# uOhm_Schematic.net
KiCad netlist of a schematic drawn in EasyEDA
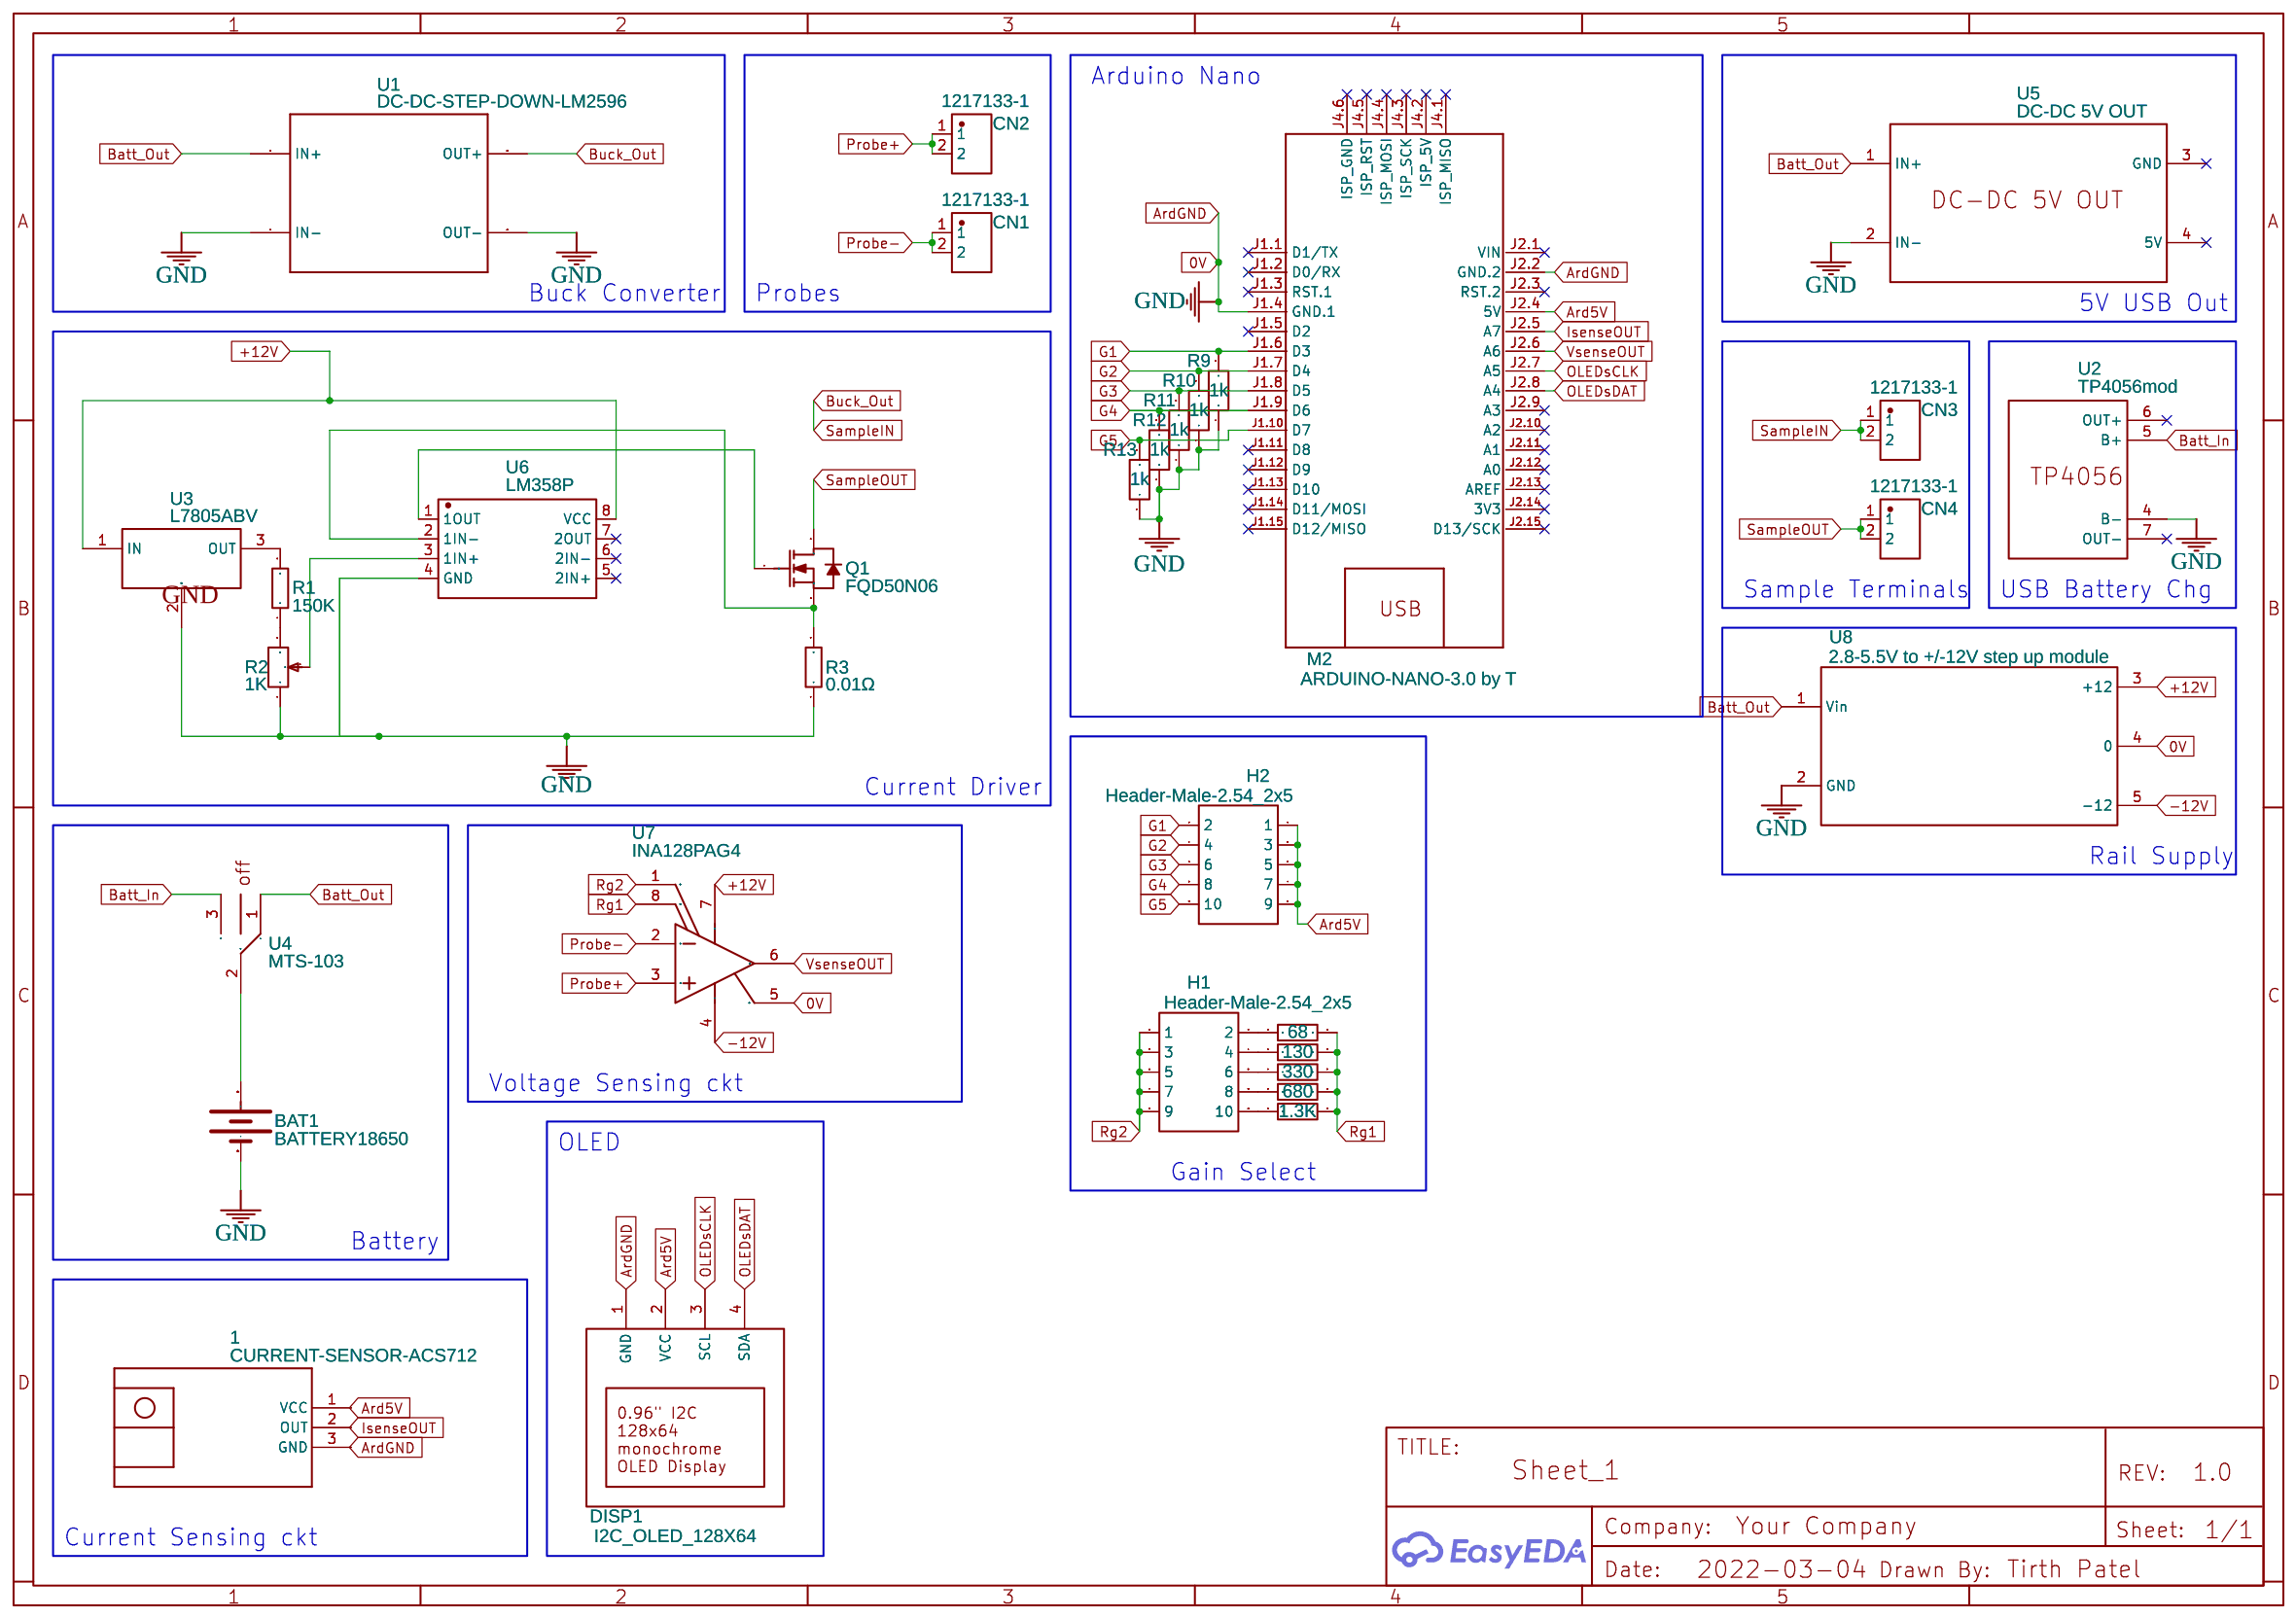
[diagram p0: schematic sheet]

(export (version "E")
  (design (tool "Eeschema 10.0.6"))
  (components
    (comp (ref "1") (value "CURRENT-SENSOR-ACS712") (libsource (lib "") (part "CURRENT-SENSOR-ACS712")))
    (comp (ref "BAT1") (value "BATTERY18650") (libsource (lib "") (part "BATTERY18650")))
    (comp (ref "CN1")
      (value "1217133-1")
      (fields (field (name "BOM_Supplier Part") "C133061"))
      (libsource (lib "") (part "1217133-1"))
    )
    (comp (ref "CN2")
      (value "1217133-1")
      (fields (field (name "BOM_Supplier Part") "C133061"))
      (libsource (lib "") (part "1217133-1"))
    )
    (comp (ref "CN3")
      (value "1217133-1")
      (fields (field (name "BOM_Supplier Part") "C133061"))
      (libsource (lib "") (part "1217133-1"))
    )
    (comp (ref "CN4")
      (value "1217133-1")
      (fields (field (name "BOM_Supplier Part") "C133061"))
      (libsource (lib "") (part "1217133-1"))
    )
    (comp (ref "DISP1") (value "I2C_OLED_128X64") (libsource (lib "") (part "I2C_OLED_128X64")))
    (comp (ref "H1")
      (value "Header-Male-2.54_2x5")
      (fields
        (field (name "BOM_Manufacturer Part") "2*5pHeaders  Pins 2.54mm")
        (field (name "BOM_Supplier Part") "C28207")
      )
      (libsource (lib "") (part "Header-Male-2.54_2x5"))
    )
    (comp (ref "H2")
      (value "Header-Male-2.54_2x5")
      (fields
        (field (name "BOM_Manufacturer Part") "2*5pHeaders  Pins 2.54mm")
        (field (name "BOM_Supplier Part") "C28207")
      )
      (libsource (lib "") (part "Header-Male-2.54_2x5_1"))
    )
    (comp (ref "M2") (value "ARDUINO-NANO-3.0 by T") (libsource (lib "") (part "ARDUINO-NANO-3.0 by T")))
    (comp (ref "Q1")
      (value "FQD50N06")
      (fields (field (name "BOM_Supplier Part") "C725048"))
      (libsource (lib "") (part "FQD50N06"))
    )
    (comp (ref "R1")
      (value "150K")
      (fields
        (field (name "BOM_Manufacturer Part") "MFR0W4F1503A50")
        (field (name "BOM_Supplier Part") "C58618")
      )
      (libsource (lib "") (part "MFR0W4F1503A50"))
    )
    (comp (ref "R2")
      (value "1K")
      (fields
        (field (name "BOM_Manufacturer Part") "3296W-1-102LF")
        (field (name "BOM_Supplier Part") "C57089")
      )
      (libsource (lib "") (part "3296W-1-102LF"))
    )
    (comp (ref "R3")
      (value "0.01Ω")
      (fields
        (field (name "BOM_Manufacturer Part") "LR2512-23R010F4")
        (field (name "BOM_Supplier Part") "C323803")
      )
      (libsource (lib "") (part "LR2512-23R010F4"))
    )
    (comp (ref "R4")
      (value "330")
      (fields
        (field (name "BOM_Manufacturer Part") "MFR1WSFTE52-330R")
        (field (name "BOM_Supplier Part") "C172941")
      )
      (libsource (lib "") (part "MFR1WSFTE52-330R"))
    )
    (comp (ref "R5")
      (value "130")
      (fields
        (field (name "BOM_Manufacturer Part") "RD50T5131J")
        (field (name "BOM_Supplier Part") "C167536")
      )
      (libsource (lib "") (part "RD50T5131J"))
    )
    (comp (ref "R6")
      (value "680")
      (fields
        (field (name "BOM_Manufacturer Part") "MFR0W4F6800A50")
        (field (name "BOM_Supplier Part") "C58599")
      )
      (libsource (lib "") (part "MFR0W4F6800A50"))
    )
    (comp (ref "R7")
      (value "68")
      (fields
        (field (name "BOM_Manufacturer Part") "RSS02J68R0A520NH")
        (field (name "BOM_Supplier Part") "C274837")
      )
      (libsource (lib "") (part "RSS02J68R0A520NH"))
    )
    (comp (ref "R8")
      (value "1.3K")
      (fields
        (field (name "BOM_Manufacturer Part") "CFR0W4J0132A50")
        (field (name "BOM_Supplier Part") "C70828")
      )
      (libsource (lib "") (part "CFR0W4J0132A50"))
    )
    (comp (ref "R9")
      (value "1k")
      (fields
        (field (name "BOM_Manufacturer Part") "CFR0W4J0102A50")
        (field (name "BOM_Supplier Part") "C66649")
      )
      (libsource (lib "") (part "CFR0W4J0102A50_C66649"))
    )
    (comp (ref "R10")
      (value "1k")
      (fields
        (field (name "BOM_Manufacturer Part") "CFR0W4J0102A50")
        (field (name "BOM_Supplier Part") "C66649")
      )
      (libsource (lib "") (part "CFR0W4J0102A50_C66649"))
    )
    (comp (ref "R11")
      (value "1k")
      (fields
        (field (name "BOM_Manufacturer Part") "CFR0W4J0102A50")
        (field (name "BOM_Supplier Part") "C66649")
      )
      (libsource (lib "") (part "CFR0W4J0102A50_C66649"))
    )
    (comp (ref "R12")
      (value "1k")
      (fields
        (field (name "BOM_Manufacturer Part") "CFR0W4J0102A50")
        (field (name "BOM_Supplier Part") "C66649")
      )
      (libsource (lib "") (part "CFR0W4J0102A50_C66649"))
    )
    (comp (ref "R13")
      (value "1k")
      (fields
        (field (name "BOM_Manufacturer Part") "CFR0W4J0102A50")
        (field (name "BOM_Supplier Part") "C66649")
      )
      (libsource (lib "") (part "CFR0W4J0102A50_C66649"))
    )
    (comp (ref "U1") (value "DC-DC-STEP-DOWN-LM2596") (libsource (lib "") (part "DC-DC-STEP-DOWN-LM2596")))
    (comp (ref "U2")
      (value "TP4056mod")
      (fields (field (name "BOM_Manufacturer Part") "TP4056-protect"))
      (libsource (lib "") (part "TP4056mod"))
    )
    (comp (ref "U3")
      (value "L7805ABV")
      (fields (field (name "BOM_Supplier Part") "C16807"))
      (libsource (lib "") (part "L7805ABV"))
    )
    (comp (ref "U4") (value "MTS-103") (libsource (lib "") (part "MTS-103")))
    (comp (ref "U5")
      (value "DC-DC 5V OUT")
      (fields (field (name "BOM_Manufacturer Part") "STEP UP"))
      (libsource (lib "") (part "DC-DC 5V OUT"))
    )
    (comp (ref "U6")
      (value "LM358P")
      (fields (field (name "BOM_Supplier Part") "C5213"))
      (libsource (lib "") (part "LM358P"))
    )
    (comp (ref "U7")
      (value "INA128PAG4")
      (fields (field (name "BOM_Supplier Part") "C28937"))
      (libsource (lib "") (part "INA128PAG4"))
    )
    (comp (ref "U8")
      (value "2.8-5.5V to +/-12V step up module")
      (libsource (lib "") (part "2.8-5.5V to +/-12V step up module"))
    )
  )
  (nets
    (net (code "1") (name "+12V") (class "Default")
      (node (ref "U3") (pin "1") (pinfunction "IN_1") (pintype "passive"))
      (node (ref "U6") (pin "8") (pinfunction "VCC_8") (pintype "unspecified"))
      (node (ref "U7") (pin "7") (pinfunction "V+_7") (pintype "passive"))
      (node (ref "U8") (pin "3") (pinfunction "+12_3") (pintype "unspecified"))
    )
    (net (code "2") (name "-12V") (class "Default")
      (node (ref "U7") (pin "4") (pinfunction "V-_4") (pintype "passive"))
      (node (ref "U8") (pin "5") (pinfunction "-12_5") (pintype "unspecified"))
    )
    (net (code "3") (name "0V") (class "Default")
      (node (ref "1") (pin "3") (pinfunction "GND_3") (pintype "bidirectional"))
      (node (ref "BAT1") (pin "GND@1") (pinfunction "-_GND@1") (pintype "passive"))
      (node (ref "DISP1") (pin "1") (pinfunction "GND_1") (pintype "unspecified"))
      (node (ref "M2") (pin "J1.4") (pinfunction "GND.1_J1.4") (pintype "bidirectional"))
      (node (ref "M2") (pin "J2.2") (pinfunction "GND.2_J2.2") (pintype "bidirectional"))
      (node (ref "R10") (pin "1") (pinfunction "1_1") (pintype "unspecified"))
      (node (ref "R11") (pin "1") (pinfunction "1_1") (pintype "unspecified"))
      (node (ref "R12") (pin "1") (pinfunction "1_1") (pintype "unspecified"))
      (node (ref "R13") (pin "1") (pinfunction "1_1") (pintype "unspecified"))
      (node (ref "R2") (pin "1") (pinfunction "1_1") (pintype "input"))
      (node (ref "R3") (pin "1") (pinfunction "1_1") (pintype "unspecified"))
      (node (ref "R9") (pin "1") (pinfunction "1_1") (pintype "unspecified"))
      (node (ref "U1") (pin "IN-") (pinfunction "IN-_IN-") (pintype "unspecified"))
      (node (ref "U1") (pin "OUT-") (pinfunction "OUT-_OUT-") (pintype "unspecified"))
      (node (ref "U2") (pin "4") (pinfunction "B-_4") (pintype "unspecified"))
      (node (ref "U3") (pin "2") (pinfunction "GND_2") (pintype "passive"))
      (node (ref "U5") (pin "2") (pinfunction "IN-_2") (pintype "unspecified"))
      (node (ref "U6") (pin "4") (pinfunction "GND_4") (pintype "unspecified"))
      (node (ref "U7") (pin "5") (pinfunction "REF_5") (pintype "unspecified"))
      (node (ref "U8") (pin "2") (pinfunction "GND_2") (pintype "unspecified"))
      (node (ref "U8") (pin "4") (pinfunction "0_4") (pintype "unspecified"))
    )
    (net (code "4") (name "Ard5V") (class "Default")
      (node (ref "1") (pin "1") (pinfunction "VCC_1") (pintype "bidirectional"))
      (node (ref "DISP1") (pin "2") (pinfunction "VCC_2") (pintype "unspecified"))
      (node (ref "H2") (pin "1") (pinfunction "1_1") (pintype "input"))
      (node (ref "H2") (pin "3") (pinfunction "3_3") (pintype "input"))
      (node (ref "H2") (pin "5") (pinfunction "5_5") (pintype "input"))
      (node (ref "H2") (pin "7") (pinfunction "7_7") (pintype "input"))
      (node (ref "H2") (pin "9") (pinfunction "9_9") (pintype "input"))
      (node (ref "M2") (pin "J2.4") (pinfunction "5V_J2.4") (pintype "bidirectional"))
    )
    (net (code "5") (name "Batt_In") (class "Default")
      (node (ref "U2") (pin "5") (pinfunction "B+_5") (pintype "unspecified"))
      (node (ref "U4") (pin "3") (pinfunction "3_3") (pintype "unspecified"))
    )
    (net (code "6") (name "Batt_Out") (class "Default")
      (node (ref "U1") (pin "IN+") (pinfunction "IN+_IN+") (pintype "unspecified"))
      (node (ref "U4") (pin "1") (pinfunction "1_1") (pintype "unspecified"))
      (node (ref "U5") (pin "1") (pinfunction "IN+_1") (pintype "unspecified"))
      (node (ref "U8") (pin "1") (pinfunction "Vin_1") (pintype "unspecified"))
    )
    (net (code "7") (name "Buck_Out") (class "Default")
      (node (ref "CN3") (pin "1") (pinfunction "1_1") (pintype "unspecified"))
      (node (ref "CN3") (pin "2") (pinfunction "2_2") (pintype "unspecified"))
      (node (ref "U1") (pin "OUT+") (pinfunction "OUT+_OUT+") (pintype "unspecified"))
    )
    (net (code "8") (name "G1") (class "Default")
      (node (ref "H2") (pin "2") (pinfunction "2_2") (pintype "input"))
      (node (ref "M2") (pin "J1.6") (pinfunction "D3_J1.6") (pintype "bidirectional"))
      (node (ref "R9") (pin "2") (pinfunction "2_2") (pintype "unspecified"))
    )
    (net (code "9") (name "G2") (class "Default")
      (node (ref "H2") (pin "4") (pinfunction "4_4") (pintype "input"))
      (node (ref "M2") (pin "J1.7") (pinfunction "D4_J1.7") (pintype "bidirectional"))
      (node (ref "R10") (pin "2") (pinfunction "2_2") (pintype "unspecified"))
    )
    (net (code "10") (name "G3") (class "Default")
      (node (ref "H2") (pin "6") (pinfunction "6_6") (pintype "input"))
      (node (ref "M2") (pin "J1.8") (pinfunction "D5_J1.8") (pintype "bidirectional"))
      (node (ref "R11") (pin "2") (pinfunction "2_2") (pintype "unspecified"))
    )
    (net (code "11") (name "G4") (class "Default")
      (node (ref "H2") (pin "8") (pinfunction "8_8") (pintype "input"))
      (node (ref "M2") (pin "J1.9") (pinfunction "D6_J1.9") (pintype "bidirectional"))
      (node (ref "R12") (pin "2") (pinfunction "2_2") (pintype "unspecified"))
    )
    (net (code "12") (name "G5") (class "Default")
      (node (ref "H2") (pin "10") (pinfunction "10_10") (pintype "input"))
      (node (ref "M2") (pin "J1.10") (pinfunction "D7_J1.10") (pintype "bidirectional"))
      (node (ref "R13") (pin "2") (pinfunction "2_2") (pintype "unspecified"))
    )
    (net (code "13") (name "IsenseOUT") (class "Default")
      (node (ref "1") (pin "2") (pinfunction "OUT_2") (pintype "bidirectional"))
      (node (ref "M2") (pin "J2.5") (pinfunction "A7_J2.5") (pintype "bidirectional"))
    )
    (net (code "14") (name "Net-(BAT1-+)") (class "Default")
      (node (ref "BAT1") (pin "PWR@1") (pinfunction "+_PWR@1") (pintype "passive"))
      (node (ref "U4") (pin "2") (pinfunction "2_2") (pintype "unspecified"))
    )
    (net (code "15") (name "Net-(H1-Pad2)") (class "Default")
      (node (ref "H1") (pin "2") (pinfunction "2_2") (pintype "input"))
      (node (ref "R7") (pin "1") (pinfunction "1_1") (pintype "unspecified"))
    )
    (net (code "16") (name "Net-(H1-Pad4)") (class "Default")
      (node (ref "H1") (pin "4") (pinfunction "4_4") (pintype "input"))
      (node (ref "R5") (pin "1") (pinfunction "1_1") (pintype "unspecified"))
    )
    (net (code "17") (name "Net-(H1-Pad6)") (class "Default")
      (node (ref "H1") (pin "6") (pinfunction "6_6") (pintype "input"))
      (node (ref "R4") (pin "1") (pinfunction "1_1") (pintype "unspecified"))
    )
    (net (code "18") (name "Net-(H1-Pad8)") (class "Default")
      (node (ref "H1") (pin "8") (pinfunction "8_8") (pintype "input"))
      (node (ref "R6") (pin "1") (pinfunction "1_1") (pintype "input"))
    )
    (net (code "19") (name "Net-(H1-Pad10)") (class "Default")
      (node (ref "H1") (pin "10") (pinfunction "10_10") (pintype "input"))
      (node (ref "R8") (pin "1") (pinfunction "1_1") (pintype "input"))
    )
    (net (code "20") (name "Net-(Q1-G)") (class "Default")
      (node (ref "Q1") (pin "1") (pinfunction "G_1") (pintype "unspecified"))
      (node (ref "U6") (pin "1") (pinfunction "1OUT_1") (pintype "unspecified"))
    )
    (net (code "21") (name "Net-(Q1-S)") (class "Default")
      (node (ref "Q1") (pin "3") (pinfunction "S_3") (pintype "unspecified"))
      (node (ref "R3") (pin "2") (pinfunction "2_2") (pintype "unspecified"))
      (node (ref "U6") (pin "2") (pinfunction "1IN-_2") (pintype "unspecified"))
    )
    (net (code "22") (name "Net-(R1-Pad1)") (class "Default")
      (node (ref "R1") (pin "1") (pinfunction "1_1") (pintype "input"))
      (node (ref "R2") (pin "3") (pinfunction "3_3") (pintype "input"))
    )
    (net (code "23") (name "Net-(U3-OUT)") (class "Default")
      (node (ref "R1") (pin "2") (pinfunction "2_2") (pintype "input"))
      (node (ref "U3") (pin "3") (pinfunction "OUT_3") (pintype "passive"))
    )
    (net (code "24") (name "Net-(U6-1IN+)") (class "Default")
      (node (ref "R2") (pin "2") (pinfunction "2_2") (pintype "input"))
      (node (ref "U6") (pin "3") (pinfunction "1IN+_3") (pintype "unspecified"))
    )
    (net (code "25") (name "OLEDsCLK") (class "Default")
      (node (ref "DISP1") (pin "3") (pinfunction "SCL_3") (pintype "unspecified"))
      (node (ref "M2") (pin "J2.7") (pinfunction "A5_J2.7") (pintype "bidirectional"))
    )
    (net (code "26") (name "OLEDsDAT") (class "Default")
      (node (ref "DISP1") (pin "4") (pinfunction "SDA_4") (pintype "unspecified"))
      (node (ref "M2") (pin "J2.8") (pinfunction "A4_J2.8") (pintype "bidirectional"))
    )
    (net (code "27") (name "Probe+") (class "Default")
      (node (ref "CN2") (pin "1") (pinfunction "1_1") (pintype "unspecified"))
      (node (ref "CN2") (pin "2") (pinfunction "2_2") (pintype "unspecified"))
      (node (ref "U7") (pin "3") (pinfunction "VIN+_3") (pintype "unspecified"))
    )
    (net (code "28") (name "Probe-") (class "Default")
      (node (ref "CN1") (pin "1") (pinfunction "1_1") (pintype "unspecified"))
      (node (ref "CN1") (pin "2") (pinfunction "2_2") (pintype "unspecified"))
      (node (ref "U7") (pin "2") (pinfunction "VIN-_2") (pintype "unspecified"))
    )
    (net (code "29") (name "Rg1") (class "Default")
      (node (ref "R4") (pin "2") (pinfunction "2_2") (pintype "unspecified"))
      (node (ref "R5") (pin "2") (pinfunction "2_2") (pintype "unspecified"))
      (node (ref "R6") (pin "2") (pinfunction "2_2") (pintype "input"))
      (node (ref "R7") (pin "2") (pinfunction "2_2") (pintype "unspecified"))
      (node (ref "R8") (pin "2") (pinfunction "2_2") (pintype "input"))
      (node (ref "U7") (pin "8") (pinfunction "RG_8") (pintype "unspecified"))
    )
    (net (code "30") (name "Rg2") (class "Default")
      (node (ref "H1") (pin "1") (pinfunction "1_1") (pintype "input"))
      (node (ref "H1") (pin "3") (pinfunction "3_3") (pintype "input"))
      (node (ref "H1") (pin "5") (pinfunction "5_5") (pintype "input"))
      (node (ref "H1") (pin "7") (pinfunction "7_7") (pintype "input"))
      (node (ref "H1") (pin "9") (pinfunction "9_9") (pintype "input"))
      (node (ref "U7") (pin "1") (pinfunction "RG_1") (pintype "unspecified"))
    )
    (net (code "31") (name "SampleOUT") (class "Default")
      (node (ref "CN4") (pin "1") (pinfunction "1_1") (pintype "unspecified"))
      (node (ref "CN4") (pin "2") (pinfunction "2_2") (pintype "unspecified"))
      (node (ref "Q1") (pin "2") (pinfunction "D_2") (pintype "unspecified"))
    )
    (net (code "32") (name "VsenseOUT") (class "Default")
      (node (ref "M2") (pin "J2.6") (pinfunction "A6_J2.6") (pintype "bidirectional"))
      (node (ref "U7") (pin "6") (pinfunction "VO_6") (pintype "output"))
    )
    (net (code "33") (name "unconnected-(M2-3V3-PadJ2.14)") (class "Default")
      (node (ref "M2") (pin "J2.14") (pinfunction "3V3_J2.14") (pintype "bidirectional+no_connect"))
    )
    (net (code "34") (name "unconnected-(M2-A0-PadJ2.12)") (class "Default")
      (node (ref "M2") (pin "J2.12") (pinfunction "A0_J2.12") (pintype "bidirectional+no_connect"))
    )
    (net (code "35") (name "unconnected-(M2-A1-PadJ2.11)") (class "Default")
      (node (ref "M2") (pin "J2.11") (pinfunction "A1_J2.11") (pintype "bidirectional+no_connect"))
    )
    (net (code "36") (name "unconnected-(M2-A2-PadJ2.10)") (class "Default")
      (node (ref "M2") (pin "J2.10") (pinfunction "A2_J2.10") (pintype "bidirectional+no_connect"))
    )
    (net (code "37") (name "unconnected-(M2-A3-PadJ2.9)") (class "Default")
      (node (ref "M2") (pin "J2.9") (pinfunction "A3_J2.9") (pintype "bidirectional+no_connect"))
    )
    (net (code "38") (name "unconnected-(M2-AREF-PadJ2.13)") (class "Default")
      (node (ref "M2") (pin "J2.13") (pinfunction "AREF_J2.13") (pintype "bidirectional+no_connect"))
    )
    (net (code "39") (name "unconnected-(M2-D0{slash}RX-PadJ1.2)") (class "Default")
      (node (ref "M2") (pin "J1.2") (pinfunction "D0/RX_J1.2") (pintype "bidirectional+no_connect"))
    )
    (net (code "40") (name "unconnected-(M2-D1{slash}TX-PadJ1.1)") (class "Default")
      (node (ref "M2") (pin "J1.1") (pinfunction "D1/TX_J1.1") (pintype "bidirectional+no_connect"))
    )
    (net (code "41") (name "unconnected-(M2-D2-PadJ1.5)") (class "Default")
      (node (ref "M2") (pin "J1.5") (pinfunction "D2_J1.5") (pintype "bidirectional+no_connect"))
    )
    (net (code "42") (name "unconnected-(M2-D8-PadJ1.11)") (class "Default")
      (node (ref "M2") (pin "J1.11") (pinfunction "D8_J1.11") (pintype "bidirectional+no_connect"))
    )
    (net (code "43") (name "unconnected-(M2-D9-PadJ1.12)") (class "Default")
      (node (ref "M2") (pin "J1.12") (pinfunction "D9_J1.12") (pintype "bidirectional+no_connect"))
    )
    (net (code "44") (name "unconnected-(M2-D10-PadJ1.13)") (class "Default")
      (node (ref "M2") (pin "J1.13") (pinfunction "D10_J1.13") (pintype "bidirectional+no_connect"))
    )
    (net (code "45") (name "unconnected-(M2-D11{slash}MOSI-PadJ1.14)") (class "Default")
      (node (ref "M2") (pin "J1.14") (pinfunction "D11/MOSI_J1.14") (pintype "bidirectional+no_connect"))
    )
    (net (code "46") (name "unconnected-(M2-D12{slash}MISO-PadJ1.15)") (class "Default")
      (node (ref "M2") (pin "J1.15") (pinfunction "D12/MISO_J1.15") (pintype "bidirectional+no_connect"))
    )
    (net (code "47") (name "unconnected-(M2-D13{slash}SCK-PadJ2.15)") (class "Default")
      (node (ref "M2") (pin "J2.15") (pinfunction "D13/SCK_J2.15") (pintype "bidirectional+no_connect"))
    )
    (net (code "48") (name "unconnected-(M2-ISP_5V-PadJ4.2)") (class "Default")
      (node (ref "M2") (pin "J4.2") (pinfunction "ISP_5V_J4.2") (pintype "bidirectional+no_connect"))
    )
    (net (code "49") (name "unconnected-(M2-ISP_GND-PadJ4.6)") (class "Default")
      (node (ref "M2") (pin "J4.6") (pinfunction "ISP_GND_J4.6") (pintype "bidirectional+no_connect"))
    )
    (net (code "50") (name "unconnected-(M2-ISP_MISO-PadJ4.1)") (class "Default")
      (node (ref "M2") (pin "J4.1") (pinfunction "ISP_MISO_J4.1") (pintype "bidirectional+no_connect"))
    )
    (net (code "51") (name "unconnected-(M2-ISP_MOSI-PadJ4.4)") (class "Default")
      (node (ref "M2") (pin "J4.4") (pinfunction "ISP_MOSI_J4.4") (pintype "bidirectional+no_connect"))
    )
    (net (code "52") (name "unconnected-(M2-ISP_RST-PadJ4.5)") (class "Default")
      (node (ref "M2") (pin "J4.5") (pinfunction "ISP_RST_J4.5") (pintype "bidirectional+no_connect"))
    )
    (net (code "53") (name "unconnected-(M2-ISP_SCK-PadJ4.3)") (class "Default")
      (node (ref "M2") (pin "J4.3") (pinfunction "ISP_SCK_J4.3") (pintype "bidirectional+no_connect"))
    )
    (net (code "54") (name "unconnected-(M2-RST.1-PadJ1.3)") (class "Default")
      (node (ref "M2") (pin "J1.3") (pinfunction "RST.1_J1.3") (pintype "bidirectional+no_connect"))
    )
    (net (code "55") (name "unconnected-(M2-RST.2-PadJ2.3)") (class "Default")
      (node (ref "M2") (pin "J2.3") (pinfunction "RST.2_J2.3") (pintype "bidirectional+no_connect"))
    )
    (net (code "56") (name "unconnected-(M2-VIN-PadJ2.1)") (class "Default")
      (node (ref "M2") (pin "J2.1") (pinfunction "VIN_J2.1") (pintype "bidirectional+no_connect"))
    )
    (net (code "57") (name "unconnected-(U2-OUT+-Pad6)") (class "Default")
      (node (ref "U2") (pin "6") (pinfunction "OUT+_6") (pintype "unspecified+no_connect"))
    )
    (net (code "58") (name "unconnected-(U2-OUT--Pad7)") (class "Default")
      (node (ref "U2") (pin "7") (pinfunction "OUT-_7") (pintype "unspecified+no_connect"))
    )
    (net (code "59") (name "unconnected-(U5-5V-Pad4)") (class "Default")
      (node (ref "U5") (pin "4") (pinfunction "5V_4") (pintype "unspecified+no_connect"))
    )
    (net (code "60") (name "unconnected-(U5-GND-Pad3)") (class "Default")
      (node (ref "U5") (pin "3") (pinfunction "GND_3") (pintype "unspecified+no_connect"))
    )
    (net (code "61") (name "unconnected-(U6-2IN+-Pad5)") (class "Default")
      (node (ref "U6") (pin "5") (pinfunction "2IN+_5") (pintype "unspecified+no_connect"))
    )
    (net (code "62") (name "unconnected-(U6-2IN--Pad6)") (class "Default")
      (node (ref "U6") (pin "6") (pinfunction "2IN-_6") (pintype "unspecified+no_connect"))
    )
    (net (code "63") (name "unconnected-(U6-2OUT-Pad7)") (class "Default")
      (node (ref "U6") (pin "7") (pinfunction "2OUT_7") (pintype "unspecified+no_connect"))
    )
  )
)
